# Reference.net
KiCad netlist of a schematic drawn in Altium Designer
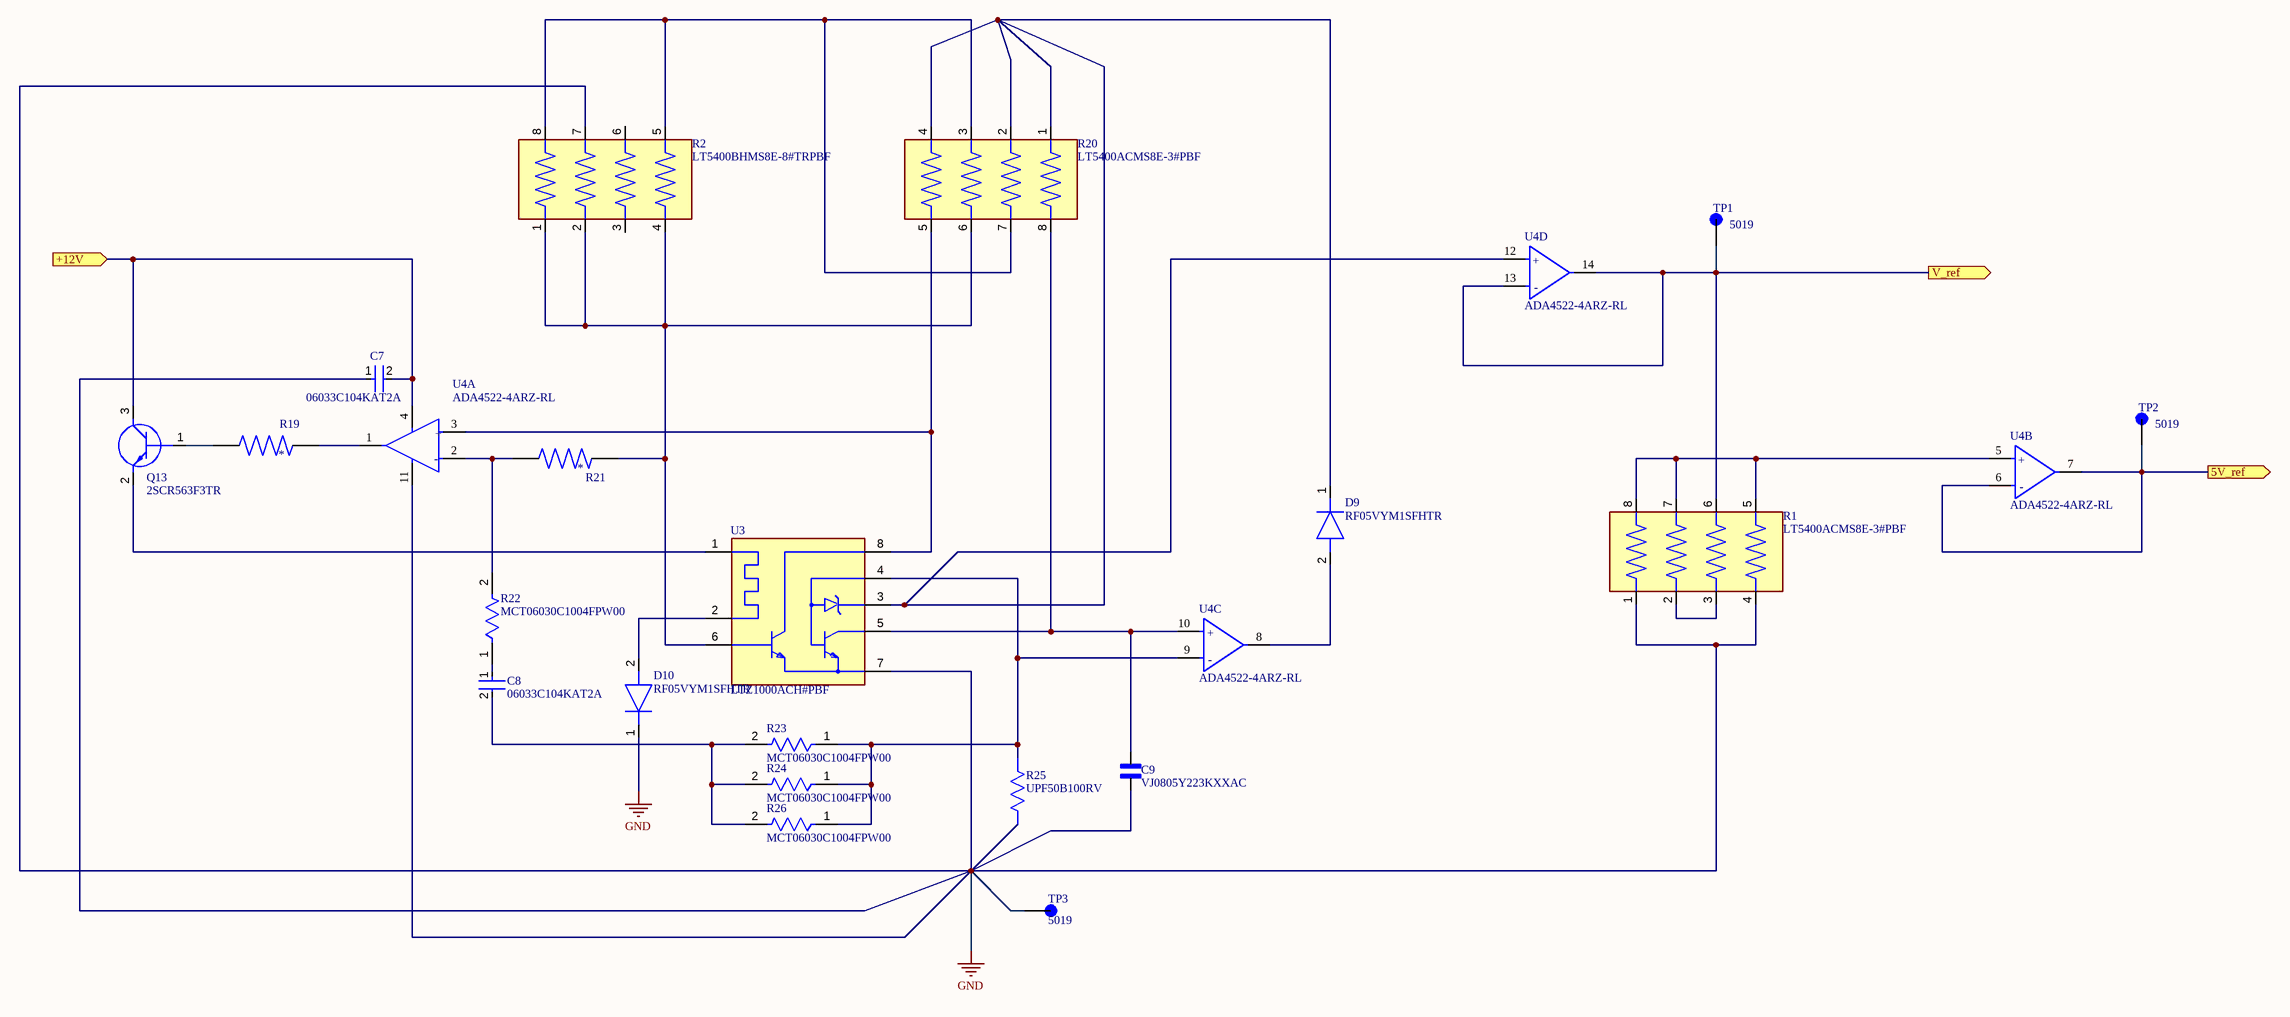
[diagram p0: Reference.SchDoc]

(export (version "E")
  (design (tool "Eeschema 10.0.6"))
  (components
    (comp (ref "C7")
      (value "06033C104KAT2A")
      (footprint "FP-0603-L_1_6_0_15-W_0_81-MFG")
      (description "General Purpose Ceramic Capacitor, 0603, 100nF, 10%, X7R, 15%, 25V")
      (fields (field (name "VOLTAGE") "25V") (field (name "TOLERANCE") "10%"))
      (libsource (lib "Altium Content Vault") (part "02cd4be3c70576c341d710602a673aa"))
    )
    (comp (ref "C8")
      (value "06033C104KAT2A")
      (footprint "FP-0603-L_1_6_0_15-W_0_81-MFG")
      (description "General Purpose Ceramic Capacitor, 0603, 100nF, 10%, X7R, 15%, 25V")
      (fields (field (name "VOLTAGE") "25V") (field (name "TOLERANCE") "10%"))
      (libsource (lib "Altium Content Vault") (part "02cd4be3c70576c341d710602a673aa"))
    )
    (comp (ref "C9")
      (value "VJ0805Y223KXXAC")
      (footprint "VJ0805Y223KXXAC:CAPC2012X145N")
      (fields (field (name "MF") "{'manufacturer': u'Vishay Vitramon'}"))
      (libsource (lib "*") (part "VJ0805Y223KXXAC"))
    )
    (comp (ref "D9")
      (value "RF05VYM1SFHTR")
      (footprint "SamacSys:RF05VYM1SFHTR")
      (description "Diode")
      (fields (field (name "MOUSER PART NUMBER") "755-RF05VYM1SFHTR"))
      (libsource (lib "*") (part "RF05VYM1SFHTR"))
    )
    (comp (ref "D10")
      (value "RF05VYM1SFHTR")
      (footprint "SamacSys:RF05VYM1SFHTR")
      (description "Diode")
      (fields (field (name "MOUSER PART NUMBER") "755-RF05VYM1SFHTR"))
      (libsource (lib "*") (part "RF05VYM1SFHTR"))
    )
    (comp (ref "Q13")
      (value "2SCR563F3TR")
      (footprint "SamacSys:2SAR542F3")
      (description "Transistor BJT NPN")
      (fields (field (name "MOUSER PART NUMBER") "755-2SCR563F3TR"))
      (libsource (lib "SamacSys") (part "2SCR563F3TR"))
    )
    (comp (ref "R1")
      (value "LT5400ACMS8E-3#PBF")
      (footprint "LT5400ACMS8E-3#PBF:SOP65P490X110-9N")
      (fields (field (name "MF") "{'manufacturer': u'Analog Devices'}"))
      (libsource (lib "*") (part "LT5400ACMS8E-3#PBF"))
    )
    (comp (ref "R2")
      (value "LT5400BHMS8E-8#TRPBF")
      (footprint "LT5400BHMS8E-8#TRPBF:SOP65P490X110-9N")
      (fields (field (name "MF") "{'manufacturer': u'Analog Devices'}"))
      (libsource (lib "*") (part "LT5400BHMS8E-8#TRPBF"))
    )
    (comp (ref "R19")
      (value "MCT06030C1001FP500")
      (footprint "MCT06030C1001FP500:RESC1508X55N")
      (description "Res Thin Film 0603 1K Ohm 1% 0.1W(1/10W) ?50ppm/C Molded SMD Automotive Medical T/R")
      (fields (field (name "ALTIUM_VALUE") "*") (field (name "MF") "{'manufacturer': u'Vishay Beyschlag'}"))
      (libsource (lib "MCT06030C1001FP500") (part "MCT06030C1001FP500"))
    )
    (comp (ref "R20")
      (value "LT5400ACMS8E-3#PBF")
      (footprint "LT5400ACMS8E-3#PBF:SOP65P490X110-9N")
      (fields (field (name "MF") "{'manufacturer': u'Analog Devices'}"))
      (libsource (lib "*") (part "LT5400ACMS8E-3#PBF"))
    )
    (comp (ref "R21")
      (value "MCT06030C1001FP500")
      (footprint "MCT06030C1001FP500:RESC1508X55N")
      (description "Res Thin Film 0603 1K Ohm 1% 0.1W(1/10W) ?50ppm/C Molded SMD Automotive Medical T/R")
      (fields (field (name "ALTIUM_VALUE") "*") (field (name "MF") "{'manufacturer': u'Vishay Beyschlag'}"))
      (libsource (lib "MCT06030C1001FP500") (part "MCT06030C1001FP500"))
    )
    (comp (ref "R22")
      (value "MCT06030C1004FPW00")
      (footprint "FP-MCT0603-MFG")
      (description "RES SMD 100 OHM 1% 1/8W 0603")
      (fields (field (name "TOLERANCE") "1%"))
      (libsource (lib "Altium Content Vault") (part "1029c3af85768c4190bb7ad29bc67b5"))
    )
    (comp (ref "R23")
      (value "MCT06030C1004FPW00")
      (footprint "FP-MCT0603-MFG")
      (description "RES SMD 100 OHM 1% 1/8W 0603")
      (fields (field (name "TOLERANCE") "1%"))
      (libsource (lib "Altium Content Vault") (part "1029c3af85768c4190bb7ad29bc67b5"))
    )
    (comp (ref "R24")
      (value "MCT06030C1004FPW00")
      (footprint "FP-MCT0603-MFG")
      (description "RES SMD 100 OHM 1% 1/8W 0603")
      (fields (field (name "TOLERANCE") "1%"))
      (libsource (lib "Altium Content Vault") (part "1029c3af85768c4190bb7ad29bc67b5"))
    )
    (comp (ref "R25")
      (value "UPF50B100RV")
      (footprint "RES_UPF50B2K0V_TEC")
      (description "No Description Available")
      (libsource (lib "UPF50B100RV") (part "UPF50B100RV"))
    )
    (comp (ref "R26")
      (value "MCT06030C1004FPW00")
      (footprint "FP-MCT0603-MFG")
      (description "RES SMD 100 OHM 1% 1/8W 0603")
      (fields (field (name "TOLERANCE") "1%"))
      (libsource (lib "Altium Content Vault") (part "1029c3af85768c4190bb7ad29bc67b5"))
    )
    (comp (ref "TP1")
      (value "5019")
      (footprint "5019:KEYSTONE_5019")
      (fields (field (name "MF") "{'manufacturer': u'Keystone Electronics'}"))
      (libsource (lib "*") (part "5019"))
    )
    (comp (ref "TP2")
      (value "5019")
      (footprint "5019:KEYSTONE_5019")
      (fields (field (name "MF") "{'manufacturer': u'Keystone Electronics'}"))
      (libsource (lib "*") (part "5019"))
    )
    (comp (ref "TP3")
      (value "5019")
      (footprint "5019:KEYSTONE_5019")
      (fields (field (name "MF") "{'manufacturer': u'Keystone Electronics'}"))
      (libsource (lib "*") (part "5019"))
    )
    (comp (ref "U3")
      (value "LTZ1000ACH#PBF")
      (footprint "FP-H-8-05-08-1320-MFG")
      (description "IC VREF SHUNT 7.2V TO5")
      (fields
        (field (name "OCTOPART") "https://octopart.com/ltz1000ach%23pbf-analog+devices-88320833")
        (field (name "MANUFACTURER") "Analog Devices")
      )
      (libsource (lib "Altium Content Vault") (part "226323f01f0396e9e7a43ae420630c2"))
    )
    (comp (ref "U4")
      (value "ADA4522-4ARZ-RL")
      (footprint "FP-R-14-IPC_C")
      (description "IC OPAMP ZERO-DRIFT 4CIRC 14SOIC")
      (libsource (lib "Altium Content Vault") (part "684fa0f315d4229452f837ea2b10642"))
    )
  )
  (nets
    (net (code "1") (name "/+12V") (class "Default")
      (node (ref "C7") (pin "2") (pinfunction "2_2") (pintype "passive"))
      (node (ref "Q13") (pin "3") (pinfunction "C_3") (pintype "passive"))
      (node (ref "U4") (pin "4") (pinfunction "V+_4") (pintype "power_in"))
    )
    (net (code "2") (name "/5V_ref") (class "Default")
      (node (ref "TP2") (pin "TP") (pinfunction "TP_TP") (pintype "passive"))
      (node (ref "U4") (pin "6") (pinfunction "-IN_B_6") (pintype "tri_state"))
      (node (ref "U4") (pin "7") (pinfunction "OUT_B_7") (pintype "passive"))
    )
    (net (code "3") (name "/V_ref") (class "Default")
      (node (ref "R1") (pin "6") (pinfunction "6_6") (pintype "passive"))
      (node (ref "TP1") (pin "TP") (pinfunction "TP_TP") (pintype "passive"))
      (node (ref "U4") (pin "13") (pinfunction "-IN_D_13") (pintype "tri_state"))
      (node (ref "U4") (pin "14") (pinfunction "OUT_D_14") (pintype "passive"))
    )
    (net (code "4") (name "GND") (class "Default")
      (node (ref "C7") (pin "1") (pinfunction "1_1") (pintype "passive"))
      (node (ref "C9") (pin "1") (pinfunction "1_1") (pintype "passive"))
      (node (ref "D10") (pin "1") (pinfunction "K_1") (pintype "passive"))
      (node (ref "R1") (pin "1") (pinfunction "1_1") (pintype "passive"))
      (node (ref "R1") (pin "4") (pinfunction "4_4") (pintype "passive"))
      (node (ref "R2") (pin "7") (pinfunction "7_7") (pintype "passive"))
      (node (ref "R25") (pin "1") (pinfunction "1_1") (pintype "passive"))
      (node (ref "TP3") (pin "TP") (pinfunction "TP_TP") (pintype "passive"))
      (node (ref "U3") (pin "7") (pinfunction "E_7") (pintype "passive"))
      (node (ref "U4") (pin "11") (pinfunction "V-_11") (pintype "power_in"))
    )
    (net (code "5") (name "Net-(C8-Pad1)") (class "Default")
      (node (ref "C8") (pin "1") (pinfunction "1_1") (pintype "passive"))
      (node (ref "R22") (pin "1") (pinfunction "1_1") (pintype "passive"))
    )
    (net (code "6") (name "Net-(C8-Pad2)") (class "Default")
      (node (ref "C8") (pin "2") (pinfunction "2_2") (pintype "passive"))
      (node (ref "R23") (pin "2") (pinfunction "2_2") (pintype "passive"))
      (node (ref "R24") (pin "2") (pinfunction "2_2") (pintype "passive"))
      (node (ref "R26") (pin "2") (pinfunction "2_2") (pintype "passive"))
    )
    (net (code "7") (name "Net-(D9-A)") (class "Default")
      (node (ref "D9") (pin "2") (pinfunction "A_2") (pintype "passive"))
      (node (ref "U4") (pin "8") (pinfunction "OUT_C_8") (pintype "passive"))
    )
    (net (code "8") (name "Net-(D9-K)") (class "Default")
      (node (ref "D9") (pin "1") (pinfunction "K_1") (pintype "passive"))
      (node (ref "R20") (pin "1") (pinfunction "1_1") (pintype "passive"))
      (node (ref "R20") (pin "2") (pinfunction "2_2") (pintype "passive"))
      (node (ref "R20") (pin "4") (pinfunction "4_4") (pintype "passive"))
      (node (ref "U3") (pin "3") (pinfunction "ZENER+_3") (pintype "passive"))
      (node (ref "U4") (pin "12") (pinfunction "+IN_D_12") (pintype "tri_state"))
    )
    (net (code "9") (name "Net-(D10-A)") (class "Default")
      (node (ref "D10") (pin "2") (pinfunction "A_2") (pintype "passive"))
      (node (ref "U3") (pin "2") (pinfunction "HEATER-_2") (pintype "passive"))
    )
    (net (code "10") (name "Net-(Q13-B)") (class "Default")
      (node (ref "Q13") (pin "1") (pinfunction "B_1") (pintype "passive"))
      (node (ref "R19") (pin "1") (pinfunction "1_1") (pintype "passive"))
    )
    (net (code "11") (name "Net-(Q13-E)") (class "Default")
      (node (ref "Q13") (pin "2") (pinfunction "E_2") (pintype "passive"))
      (node (ref "U3") (pin "1") (pinfunction "HEATER+_1") (pintype "passive"))
    )
    (net (code "12") (name "Net-(R1-Pad2)") (class "Default")
      (node (ref "R1") (pin "2") (pinfunction "2_2") (pintype "passive"))
      (node (ref "R1") (pin "3") (pinfunction "3_3") (pintype "passive"))
    )
    (net (code "13") (name "Net-(R2-Pad5)") (class "Default")
      (node (ref "R2") (pin "5") (pinfunction "5_5") (pintype "passive"))
      (node (ref "R2") (pin "8") (pinfunction "8_8") (pintype "passive"))
      (node (ref "R20") (pin "3") (pinfunction "3_3") (pintype "passive"))
      (node (ref "R20") (pin "7") (pinfunction "7_7") (pintype "passive"))
    )
    (net (code "14") (name "Net-(U3-B)") (class "Default")
      (node (ref "R2") (pin "1") (pinfunction "1_1") (pintype "passive"))
      (node (ref "R2") (pin "2") (pinfunction "2_2") (pintype "passive"))
      (node (ref "R2") (pin "4") (pinfunction "4_4") (pintype "passive"))
      (node (ref "R20") (pin "6") (pinfunction "6_6") (pintype "passive"))
      (node (ref "R21") (pin "2") (pinfunction "2_2") (pintype "passive"))
      (node (ref "U3") (pin "6") (pinfunction "B_6") (pintype "passive"))
    )
    (net (code "15") (name "Net-(U3-SUBSTRATE{slash}ZENER-)") (class "Default")
      (node (ref "R23") (pin "1") (pinfunction "1_1") (pintype "passive"))
      (node (ref "R24") (pin "1") (pinfunction "1_1") (pintype "passive"))
      (node (ref "R25") (pin "2") (pinfunction "2_2") (pintype "passive"))
      (node (ref "R26") (pin "1") (pinfunction "1_1") (pintype "passive"))
      (node (ref "U3") (pin "4") (pinfunction "SUBSTRATE/ZENER-_4") (pintype "passive"))
      (node (ref "U4") (pin "9") (pinfunction "-IN_C_9") (pintype "tri_state"))
    )
    (net (code "16") (name "Net-(U4A-+IN_A)") (class "Default")
      (node (ref "R20") (pin "5") (pinfunction "5_5") (pintype "passive"))
      (node (ref "U3") (pin "8") (pinfunction "C_8") (pintype "passive"))
      (node (ref "U4") (pin "3") (pinfunction "+IN_A_3") (pintype "tri_state"))
    )
    (net (code "17") (name "Net-(U4A--IN_A)") (class "Default")
      (node (ref "R21") (pin "1") (pinfunction "1_1") (pintype "passive"))
      (node (ref "R22") (pin "2") (pinfunction "2_2") (pintype "passive"))
      (node (ref "U4") (pin "2") (pinfunction "-IN_A_2") (pintype "tri_state"))
    )
    (net (code "18") (name "Net-(U4A-OUT_A)") (class "Default")
      (node (ref "R19") (pin "2") (pinfunction "2_2") (pintype "passive"))
      (node (ref "U4") (pin "1") (pinfunction "OUT_A_1") (pintype "passive"))
    )
    (net (code "19") (name "Net-(U4B-+IN_B)") (class "Default")
      (node (ref "R1") (pin "5") (pinfunction "5_5") (pintype "passive"))
      (node (ref "R1") (pin "7") (pinfunction "7_7") (pintype "passive"))
      (node (ref "R1") (pin "8") (pinfunction "8_8") (pintype "passive"))
      (node (ref "U4") (pin "5") (pinfunction "+IN_B_5") (pintype "tri_state"))
    )
    (net (code "20") (name "Net-(U4C-+IN_C)") (class "Default")
      (node (ref "C9") (pin "2") (pinfunction "2_2") (pintype "passive"))
      (node (ref "R20") (pin "8") (pinfunction "8_8") (pintype "passive"))
      (node (ref "U3") (pin "5") (pinfunction "C_5") (pintype "passive"))
      (node (ref "U4") (pin "10") (pinfunction "+IN_C_10") (pintype "tri_state"))
    )
    (net (code "21") (name "unconnected-(Q13-C_2-Pad4)") (class "Default")
      (node (ref "Q13") (pin "4") (pinfunction "C_2_4") (pintype "passive"))
    )
    (net (code "22") (name "unconnected-(R2-Pad3)") (class "Default")
      (node (ref "R2") (pin "3") (pinfunction "3_3") (pintype "passive"))
    )
    (net (code "23") (name "unconnected-(R2-Pad6)") (class "Default")
      (node (ref "R2") (pin "6") (pinfunction "6_6") (pintype "passive"))
    )
  )
)
